# BT_USB_All_SMD.net
KiCad netlist of a schematic drawn in EAGLE
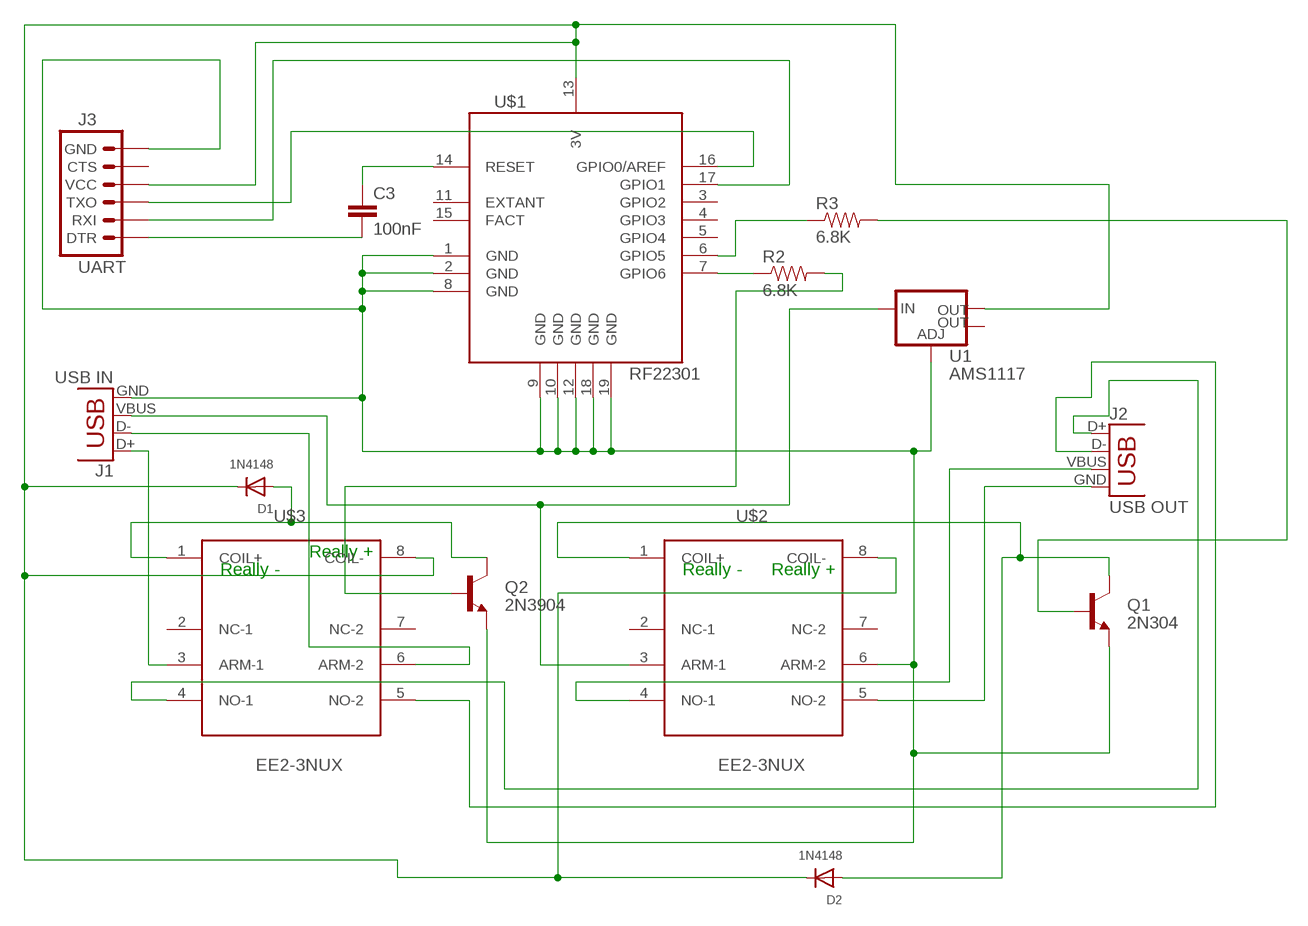
[diagram p0: schematic, sheet 1]

(export (version "E")
  (design (tool "Eeschema 10.0.6"))
  (components
    (comp (ref "C3")
      (value "100nF")
      (footprint "eagle-import:0805")
      (libsource (lib "eagle-import") (part "CAP0805"))
    )
    (comp (ref "D1")
      (value "1N4148")
      (footprint "eagle-import:SOD-123")
      (libsource (lib "eagle-import") (part "DIODESOD-123"))
    )
    (comp (ref "D2")
      (value "1N4148")
      (footprint "eagle-import:SOD-123")
      (libsource (lib "eagle-import") (part "DIODESOD-123"))
    )
    (comp (ref "J1")
      (value "USB IN")
      (footprint "eagle-import:USB-A-H")
      (libsource (lib "eagle-import") (part "USB-A-H"))
    )
    (comp (ref "J2")
      (value "USB OUT")
      (footprint "eagle-import:USB-A-S")
      (libsource (lib "eagle-import") (part "USB-A-S"))
    )
    (comp (ref "J3")
      (value "UART")
      (footprint "eagle-import:1X06")
      (libsource (lib "eagle-import") (part "ARDUINO_SERIAL_PROGRAMPTH"))
    )
    (comp (ref "Q1")
      (value "2N304")
      (footprint "eagle-import:SOT23-3")
      (libsource (lib "eagle-import") (part "TRANSISTOR_NPNMMBT5088"))
    )
    (comp (ref "Q2")
      (value "2N3904")
      (footprint "eagle-import:SOT23-3")
      (libsource (lib "eagle-import") (part "TRANSISTOR_NPNMMBT5088"))
    )
    (comp (ref "R2")
      (value "6.8K")
      (footprint "eagle-import:0805")
      (libsource (lib "eagle-import") (part "SparkFun-Resistors_RESISTOR0805-RES"))
    )
    (comp (ref "R3")
      (value "6.8K")
      (footprint "eagle-import:0805")
      (libsource (lib "eagle-import") (part "RESISTOR0805-RES"))
    )
    (comp (ref "U$1")
      (value "RF22301")
      (footprint "eagle-import:RFD22301")
      (libsource (lib "eagle-import") (part "RF22301"))
    )
    (comp (ref "U$2")
      (value "RELAY-EE2-3NUX")
      (footprint "eagle-import:RELAY-EE2-3NUX")
      (libsource (lib "eagle-import") (part "RELAY-EE2-3NUX"))
    )
    (comp (ref "U$3")
      (value "RELAY-EE2-3NUX")
      (footprint "eagle-import:RELAY-EE2-3NUX")
      (libsource (lib "eagle-import") (part "RELAY-EE2-3NUX"))
    )
    (comp (ref "U1")
      (value "AMS1117")
      (footprint "eagle-import:SOT223")
      (libsource (lib "eagle-import") (part "V_REG_LM1117SOT223"))
    )
  )
  (nets
    (net (code "1") (name "Net-(J3-DTR)") (class "Default")
      (node (ref "C3") (pin "2") (pinfunction "2_2") (pintype "passive"))
      (node (ref "J3") (pin "1") (pinfunction "DTR_1") (pintype "passive"))
    )
    (net (code "2") (name "Net-(J3-GND)") (class "Default")
      (node (ref "J1") (pin "GND") (pinfunction "GND_GND") (pintype "bidirectional"))
      (node (ref "J3") (pin "6") (pinfunction "GND_6") (pintype "passive"))
      (node (ref "Q1") (pin "2") (pinfunction "E_2") (pintype "passive"))
      (node (ref "Q2") (pin "2") (pinfunction "E_2") (pintype "passive"))
      (node (ref "U$1") (pin "1") (pinfunction "GND_1") (pintype "power_in"))
      (node (ref "U$1") (pin "10") (pinfunction "GND_10") (pintype "power_in"))
      (node (ref "U$1") (pin "12") (pinfunction "GND_12") (pintype "power_in"))
      (node (ref "U$1") (pin "18") (pinfunction "GND_18") (pintype "power_in"))
      (node (ref "U$1") (pin "19") (pinfunction "GND_19") (pintype "power_in"))
      (node (ref "U$1") (pin "2") (pinfunction "GND_2") (pintype "power_in"))
      (node (ref "U$1") (pin "8") (pinfunction "GND_8") (pintype "power_in"))
      (node (ref "U$1") (pin "9") (pinfunction "GND_9") (pintype "power_in"))
      (node (ref "U$2") (pin "6") (pinfunction "ARM-2_6") (pintype "bidirectional"))
      (node (ref "U1") (pin "1") (pinfunction "ADJ_1") (pintype "input"))
    )
    (net (code "3") (name "Net-(J3-RXI)") (class "Default")
      (node (ref "J3") (pin "2") (pinfunction "RXI_2") (pintype "passive"))
      (node (ref "U$1") (pin "17") (pinfunction "GPIO1_17") (pintype "bidirectional"))
    )
    (net (code "4") (name "Net-(J3-TXO)") (class "Default")
      (node (ref "J3") (pin "3") (pinfunction "TXO_3") (pintype "passive"))
      (node (ref "U$1") (pin "16") (pinfunction "GPIO0/AREF_16") (pintype "bidirectional"))
    )
    (net (code "5") (name "Net-(J3-VCC)") (class "Default")
      (node (ref "D1") (pin "C") (pinfunction "C_C") (pintype "passive"))
      (node (ref "D2") (pin "C") (pinfunction "C_C") (pintype "passive"))
      (node (ref "J3") (pin "4") (pinfunction "VCC_4") (pintype "passive"))
      (node (ref "U$1") (pin "13") (pinfunction "3V_13") (pintype "bidirectional"))
      (node (ref "U$2") (pin "8") (pinfunction "COIL-_8") (pintype "bidirectional"))
      (node (ref "U$3") (pin "8") (pinfunction "COIL-_8") (pintype "bidirectional"))
      (node (ref "U1") (pin "2") (pinfunction "OUT_2") (pintype "output"))
    )
    (net (code "6") (name "Net-(Q1-B)") (class "Default")
      (node (ref "Q1") (pin "1") (pinfunction "B_1") (pintype "passive"))
      (node (ref "R3") (pin "2") (pinfunction "2_2") (pintype "passive"))
    )
    (net (code "7") (name "Net-(Q1-C)") (class "Default")
      (node (ref "D2") (pin "A") (pinfunction "A_A") (pintype "passive"))
      (node (ref "Q1") (pin "3") (pinfunction "C_3") (pintype "passive"))
      (node (ref "U$2") (pin "1") (pinfunction "COIL+_1") (pintype "bidirectional"))
    )
    (net (code "8") (name "Net-(Q2-B)") (class "Default")
      (node (ref "Q2") (pin "1") (pinfunction "B_1") (pintype "passive"))
      (node (ref "R2") (pin "2") (pinfunction "2_2") (pintype "passive"))
    )
    (net (code "9") (name "Net-(Q2-C)") (class "Default")
      (node (ref "D1") (pin "A") (pinfunction "A_A") (pintype "passive"))
      (node (ref "Q2") (pin "3") (pinfunction "C_3") (pintype "passive"))
      (node (ref "U$3") (pin "1") (pinfunction "COIL+_1") (pintype "bidirectional"))
    )
    (net (code "10") (name "Net-(U$1-GPIO5)") (class "Default")
      (node (ref "R3") (pin "1") (pinfunction "1_1") (pintype "passive"))
      (node (ref "U$1") (pin "6") (pinfunction "GPIO5_6") (pintype "bidirectional"))
    )
    (net (code "11") (name "Net-(U$1-GPIO6)") (class "Default")
      (node (ref "R2") (pin "1") (pinfunction "1_1") (pintype "passive"))
      (node (ref "U$1") (pin "7") (pinfunction "GPIO6_7") (pintype "bidirectional"))
    )
    (net (code "12") (name "Net-(U$1-RESET)") (class "Default")
      (node (ref "C3") (pin "1") (pinfunction "1_1") (pintype "passive"))
      (node (ref "U$1") (pin "14") (pinfunction "RESET_14") (pintype "bidirectional"))
    )
    (net (code "13") (name "Net-(U$2-ARM-1)") (class "Default")
      (node (ref "J1") (pin "VBUS") (pinfunction "VBUS_VBUS") (pintype "bidirectional"))
      (node (ref "U$2") (pin "3") (pinfunction "ARM-1_3") (pintype "bidirectional"))
      (node (ref "U1") (pin "3") (pinfunction "IN_3") (pintype "input"))
    )
    (net (code "14") (name "Net-(U$2-NO-1)") (class "Default")
      (node (ref "J2") (pin "VBUS") (pinfunction "VBUS_VBUS") (pintype "bidirectional"))
      (node (ref "U$2") (pin "4") (pinfunction "NO-1_4") (pintype "bidirectional"))
    )
    (net (code "15") (name "Net-(U$2-NO-2)") (class "Default")
      (node (ref "J2") (pin "GND") (pinfunction "GND_GND") (pintype "bidirectional"))
      (node (ref "U$2") (pin "5") (pinfunction "NO-2_5") (pintype "bidirectional"))
    )
    (net (code "16") (name "Net-(U$3-ARM-1)") (class "Default")
      (node (ref "J1") (pin "D+") (pinfunction "D+_D+") (pintype "bidirectional"))
      (node (ref "U$3") (pin "3") (pinfunction "ARM-1_3") (pintype "bidirectional"))
    )
    (net (code "17") (name "Net-(U$3-ARM-2)") (class "Default")
      (node (ref "J1") (pin "D-") (pinfunction "D-_D-") (pintype "bidirectional"))
      (node (ref "U$3") (pin "6") (pinfunction "ARM-2_6") (pintype "bidirectional"))
    )
    (net (code "18") (name "Net-(U$3-NO-1)") (class "Default")
      (node (ref "J2") (pin "D+") (pinfunction "D+_D+") (pintype "bidirectional"))
      (node (ref "U$3") (pin "4") (pinfunction "NO-1_4") (pintype "bidirectional"))
    )
    (net (code "19") (name "Net-(U$3-NO-2)") (class "Default")
      (node (ref "J2") (pin "D-") (pinfunction "D-_D-") (pintype "bidirectional"))
      (node (ref "U$3") (pin "5") (pinfunction "NO-2_5") (pintype "bidirectional"))
    )
    (net (code "20") (name "unconnected-(J3-CTS-Pad5)") (class "Default")
      (node (ref "J3") (pin "5") (pinfunction "CTS_5") (pintype "passive"))
    )
    (net (code "21") (name "unconnected-(U$1-EXTANT-Pad11)") (class "Default")
      (node (ref "U$1") (pin "11") (pinfunction "EXTANT_11") (pintype "bidirectional"))
    )
    (net (code "22") (name "unconnected-(U$1-FACT-Pad15)") (class "Default")
      (node (ref "U$1") (pin "15") (pinfunction "FACT_15") (pintype "bidirectional"))
    )
    (net (code "23") (name "unconnected-(U$1-GPIO2-Pad3)") (class "Default")
      (node (ref "U$1") (pin "3") (pinfunction "GPIO2_3") (pintype "bidirectional"))
    )
    (net (code "24") (name "unconnected-(U$1-GPIO3-Pad4)") (class "Default")
      (node (ref "U$1") (pin "4") (pinfunction "GPIO3_4") (pintype "bidirectional"))
    )
    (net (code "25") (name "unconnected-(U$1-GPIO4-Pad5)") (class "Default")
      (node (ref "U$1") (pin "5") (pinfunction "GPIO4_5") (pintype "bidirectional"))
    )
    (net (code "26") (name "unconnected-(U$2-NC-1-Pad2)") (class "Default")
      (node (ref "U$2") (pin "2") (pinfunction "NC-1_2") (pintype "bidirectional"))
    )
    (net (code "27") (name "unconnected-(U$2-NC-2-Pad7)") (class "Default")
      (node (ref "U$2") (pin "7") (pinfunction "NC-2_7") (pintype "bidirectional"))
    )
    (net (code "28") (name "unconnected-(U$3-NC-1-Pad2)") (class "Default")
      (node (ref "U$3") (pin "2") (pinfunction "NC-1_2") (pintype "bidirectional"))
    )
    (net (code "29") (name "unconnected-(U$3-NC-2-Pad7)") (class "Default")
      (node (ref "U$3") (pin "7") (pinfunction "NC-2_7") (pintype "bidirectional"))
    )
    (net (code "30") (name "unconnected-(U1-OUT-Pad4)") (class "Default")
      (node (ref "U1") (pin "4") (pinfunction "OUT_4") (pintype "output"))
    )
  )
)
